# P0_1.net
KiCad netlist of a schematic drawn in EAGLE
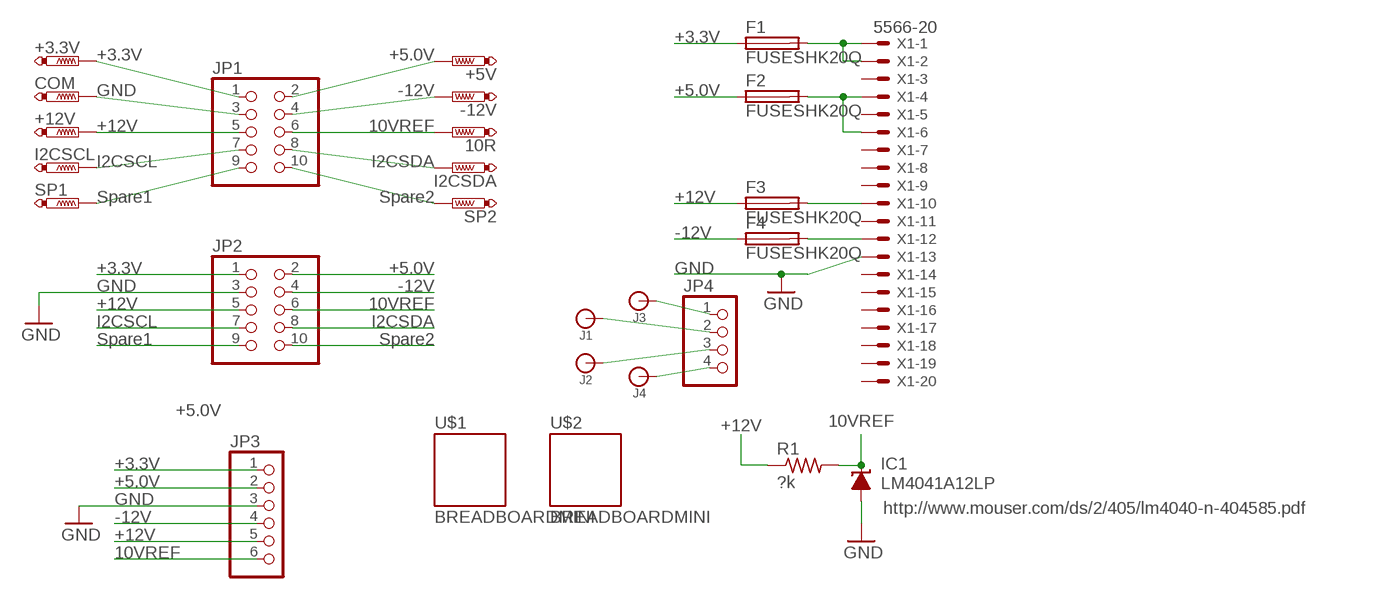
[diagram p0: schematic, sheet 1]

(export (version "E")
  (design (tool "Eeschema 10.0.6"))
  (components
    (comp (ref "+3.3V")
      (value "PTR1B1,27")
      (footprint "eagle-import:B1,27")
      (libsource (lib "eagle-import") (part "PTR1B1,27"))
    )
    (comp (ref "+5V")
      (value "PTR1B1,27")
      (footprint "eagle-import:B1,27")
      (libsource (lib "eagle-import") (part "PTR1B1,27"))
    )
    (comp (ref "+12V")
      (value "PTR1B1,27")
      (footprint "eagle-import:B1,27")
      (libsource (lib "eagle-import") (part "PTR1B1,27"))
    )
    (comp (ref "-12V")
      (value "PTR1B1,27")
      (footprint "eagle-import:B1,27")
      (libsource (lib "eagle-import") (part "PTR1B1,27"))
    )
    (comp (ref "10R")
      (value "PTR1B1,27")
      (footprint "eagle-import:B1,27")
      (libsource (lib "eagle-import") (part "PTR1B1,27"))
    )
    (comp (ref "COM")
      (value "PTR1B1,27")
      (footprint "eagle-import:B1,27")
      (libsource (lib "eagle-import") (part "PTR1B1,27"))
    )
    (comp (ref "F1")
      (value "FUSESHK20Q")
      (footprint "eagle-import:SHK20Q")
      (libsource (lib "eagle-import") (part "FUSESHK20Q"))
    )
    (comp (ref "F2")
      (value "FUSESHK20Q")
      (footprint "eagle-import:SHK20Q")
      (libsource (lib "eagle-import") (part "FUSESHK20Q"))
    )
    (comp (ref "F3")
      (value "FUSESHK20Q")
      (footprint "eagle-import:SHK20Q")
      (libsource (lib "eagle-import") (part "FUSESHK20Q"))
    )
    (comp (ref "F4")
      (value "FUSESHK20Q")
      (footprint "eagle-import:SHK20Q")
      (libsource (lib "eagle-import") (part "FUSESHK20Q"))
    )
    (comp (ref "I2CSCL")
      (value "PTR1B1,27")
      (footprint "eagle-import:B1,27")
      (libsource (lib "eagle-import") (part "PTR1B1,27"))
    )
    (comp (ref "I2CSDA")
      (value "PTR1B1,27")
      (footprint "eagle-import:B1,27")
      (libsource (lib "eagle-import") (part "PTR1B1,27"))
    )
    (comp (ref "IC1")
      (value "LM4041A12LP")
      (footprint "eagle-import:LP_O-PBCY-W3")
      (libsource (lib "eagle-import") (part "LM4041LPA12"))
    )
    (comp (ref "J1")
      (value "BANANA_CONN")
      (footprint "eagle-import:BANANA_CONN")
      (libsource (lib "eagle-import") (part "BANANA_CONN"))
    )
    (comp (ref "J2")
      (value "BANANA_CONN")
      (footprint "eagle-import:BANANA_CONN")
      (libsource (lib "eagle-import") (part "BANANA_CONN"))
    )
    (comp (ref "J3")
      (value "BANANA_CONN")
      (footprint "eagle-import:BANANA_CONN")
      (libsource (lib "eagle-import") (part "BANANA_CONN"))
    )
    (comp (ref "J4")
      (value "BANANA_CONN")
      (footprint "eagle-import:BANANA_CONN")
      (libsource (lib "eagle-import") (part "BANANA_CONN"))
    )
    (comp (ref "JP1")
      (value "PINHD-2X5/90")
      (footprint "eagle-import:2X05_90")
      (libsource (lib "eagle-import") (part "PINHD-2X5/90"))
    )
    (comp (ref "JP2")
      (value "PINHD-2X5/90")
      (footprint "eagle-import:2X05_90")
      (libsource (lib "eagle-import") (part "PINHD-2X5/90"))
    )
    (comp (ref "JP3")
      (value "PINHD-1X6")
      (footprint "eagle-import:1X06")
      (libsource (lib "eagle-import") (part "PINHD-1X6"))
    )
    (comp (ref "JP4")
      (value "PINHD-1X4")
      (footprint "eagle-import:1X04")
      (libsource (lib "eagle-import") (part "PINHD-1X4"))
    )
    (comp (ref "R1")
      (value "?k")
      (footprint "eagle-import:0204_7")
      (libsource (lib "eagle-import") (part "R-US_0204/7"))
    )
    (comp (ref "SP1")
      (value "PTR1B1,27")
      (footprint "eagle-import:B1,27")
      (libsource (lib "eagle-import") (part "PTR1B1,27"))
    )
    (comp (ref "SP2")
      (value "PTR1B1,27")
      (footprint "eagle-import:B1,27")
      (libsource (lib "eagle-import") (part "PTR1B1,27"))
    )
    (comp (ref "U$1")
      (value "BREADBOARDMINI")
      (footprint "eagle-import:BREADBOARD-MINI")
      (libsource (lib "eagle-import") (part "BREADBOARDMINI"))
    )
    (comp (ref "U$2")
      (value "BREADBOARDMINI")
      (footprint "eagle-import:BREADBOARD-MINI")
      (libsource (lib "eagle-import") (part "BREADBOARDMINI"))
    )
    (comp (ref "X1")
      (value "5566-20")
      (footprint "eagle-import:5566-20")
      (libsource (lib "eagle-import") (part "5566-20"))
    )
  )
  (nets
    (net (code "1") (name "/+3.3V") (class "Default")
      (node (ref "+3.3V") (pin "TP") (pinfunction "TP_TP") (pintype "input"))
      (node (ref "F1") (pin "1A") (pinfunction "1_1A") (pintype "passive"))
      (node (ref "JP1") (pin "1") (pinfunction "1_1") (pintype "passive"))
      (node (ref "JP2") (pin "1") (pinfunction "1_1") (pintype "passive"))
      (node (ref "JP3") (pin "1") (pinfunction "1_1") (pintype "passive"))
    )
    (net (code "2") (name "/+5.0V") (class "Default")
      (node (ref "+5V") (pin "TP") (pinfunction "TP_TP") (pintype "input"))
      (node (ref "F2") (pin "1A") (pinfunction "1_1A") (pintype "passive"))
      (node (ref "JP1") (pin "2") (pinfunction "2_2") (pintype "passive"))
      (node (ref "JP2") (pin "2") (pinfunction "2_2") (pintype "passive"))
      (node (ref "JP3") (pin "2") (pinfunction "2_2") (pintype "passive"))
    )
    (net (code "3") (name "/+12V") (class "Default")
      (node (ref "+12V") (pin "TP") (pinfunction "TP_TP") (pintype "input"))
      (node (ref "F3") (pin "1A") (pinfunction "1_1A") (pintype "passive"))
      (node (ref "JP1") (pin "5") (pinfunction "5_5") (pintype "passive"))
      (node (ref "JP2") (pin "5") (pinfunction "5_5") (pintype "passive"))
      (node (ref "JP3") (pin "5") (pinfunction "5_5") (pintype "passive"))
      (node (ref "R1") (pin "1") (pinfunction "1_1") (pintype "passive"))
    )
    (net (code "4") (name "/-12V") (class "Default")
      (node (ref "-12V") (pin "TP") (pinfunction "TP_TP") (pintype "input"))
      (node (ref "F4") (pin "1A") (pinfunction "1_1A") (pintype "passive"))
      (node (ref "JP1") (pin "4") (pinfunction "4_4") (pintype "passive"))
      (node (ref "JP2") (pin "4") (pinfunction "4_4") (pintype "passive"))
      (node (ref "JP3") (pin "4") (pinfunction "4_4") (pintype "passive"))
    )
    (net (code "5") (name "/10VREF") (class "Default")
      (node (ref "10R") (pin "TP") (pinfunction "TP_TP") (pintype "input"))
      (node (ref "IC1") (pin "2") (pinfunction "C_2") (pintype "passive"))
      (node (ref "JP1") (pin "6") (pinfunction "6_6") (pintype "passive"))
      (node (ref "JP2") (pin "6") (pinfunction "6_6") (pintype "passive"))
      (node (ref "JP3") (pin "6") (pinfunction "6_6") (pintype "passive"))
      (node (ref "R1") (pin "2") (pinfunction "2_2") (pintype "passive"))
    )
    (net (code "6") (name "/I2CSCL") (class "Default")
      (node (ref "I2CSCL") (pin "TP") (pinfunction "TP_TP") (pintype "input"))
      (node (ref "JP1") (pin "7") (pinfunction "7_7") (pintype "passive"))
      (node (ref "JP2") (pin "7") (pinfunction "7_7") (pintype "passive"))
    )
    (net (code "7") (name "/I2CSDA") (class "Default")
      (node (ref "I2CSDA") (pin "TP") (pinfunction "TP_TP") (pintype "input"))
      (node (ref "JP1") (pin "8") (pinfunction "8_8") (pintype "passive"))
      (node (ref "JP2") (pin "8") (pinfunction "8_8") (pintype "passive"))
    )
    (net (code "8") (name "/SPARE1") (class "Default")
      (node (ref "JP1") (pin "9") (pinfunction "9_9") (pintype "passive"))
      (node (ref "JP2") (pin "9") (pinfunction "9_9") (pintype "passive"))
      (node (ref "SP1") (pin "TP") (pinfunction "TP_TP") (pintype "input"))
    )
    (net (code "9") (name "/SPARE2") (class "Default")
      (node (ref "JP1") (pin "10") (pinfunction "10_10") (pintype "passive"))
      (node (ref "JP2") (pin "10") (pinfunction "10_10") (pintype "passive"))
      (node (ref "SP2") (pin "TP") (pinfunction "TP_TP") (pintype "input"))
    )
    (net (code "10") (name "GND") (class "Default")
      (node (ref "COM") (pin "TP") (pinfunction "TP_TP") (pintype "input"))
      (node (ref "IC1") (pin "3") (pinfunction "A_3") (pintype "passive"))
      (node (ref "JP1") (pin "3") (pinfunction "3_3") (pintype "passive"))
      (node (ref "JP2") (pin "3") (pinfunction "3_3") (pintype "passive"))
      (node (ref "JP3") (pin "3") (pinfunction "3_3") (pintype "passive"))
      (node (ref "X1") (pin "13") (pinfunction "S_13") (pintype "passive"))
    )
    (net (code "11") (name "Net-(F1-2)") (class "Default")
      (node (ref "F1") (pin "2A") (pinfunction "2_2A") (pintype "passive"))
      (node (ref "X1") (pin "1") (pinfunction "S_1") (pintype "passive"))
      (node (ref "X1") (pin "2") (pinfunction "S_2") (pintype "passive"))
    )
    (net (code "12") (name "Net-(F2-2)") (class "Default")
      (node (ref "F2") (pin "2A") (pinfunction "2_2A") (pintype "passive"))
      (node (ref "X1") (pin "4") (pinfunction "S_4") (pintype "passive"))
      (node (ref "X1") (pin "6") (pinfunction "S_6") (pintype "passive"))
    )
    (net (code "13") (name "Net-(F3-2)") (class "Default")
      (node (ref "F3") (pin "2A") (pinfunction "2_2A") (pintype "passive"))
      (node (ref "X1") (pin "10") (pinfunction "S_10") (pintype "passive"))
    )
    (net (code "14") (name "Net-(F4-2)") (class "Default")
      (node (ref "F4") (pin "2A") (pinfunction "2_2A") (pintype "passive"))
      (node (ref "X1") (pin "12") (pinfunction "S_12") (pintype "passive"))
    )
    (net (code "15") (name "Net-(J1-1)") (class "Default")
      (node (ref "J1") (pin "P$1") (pinfunction "1_P$1") (pintype "passive"))
      (node (ref "JP4") (pin "2") (pinfunction "2_2") (pintype "passive"))
    )
    (net (code "16") (name "Net-(J2-1)") (class "Default")
      (node (ref "J2") (pin "P$1") (pinfunction "1_P$1") (pintype "passive"))
      (node (ref "JP4") (pin "3") (pinfunction "3_3") (pintype "passive"))
    )
    (net (code "17") (name "Net-(J3-1)") (class "Default")
      (node (ref "J3") (pin "P$1") (pinfunction "1_P$1") (pintype "passive"))
      (node (ref "JP4") (pin "1") (pinfunction "1_1") (pintype "passive"))
    )
    (net (code "18") (name "Net-(J4-1)") (class "Default")
      (node (ref "J4") (pin "P$1") (pinfunction "1_P$1") (pintype "passive"))
      (node (ref "JP4") (pin "4") (pinfunction "4_4") (pintype "passive"))
    )
    (net (code "19") (name "unconnected-(X1C-S-Pad11)") (class "Default")
      (node (ref "X1") (pin "11") (pinfunction "S_11") (pintype "passive"))
    )
    (net (code "20") (name "unconnected-(X1F-S-Pad14)") (class "Default")
      (node (ref "X1") (pin "14") (pinfunction "S_14") (pintype "passive"))
    )
    (net (code "21") (name "unconnected-(X1G-S-Pad15)") (class "Default")
      (node (ref "X1") (pin "15") (pinfunction "S_15") (pintype "passive"))
    )
    (net (code "22") (name "unconnected-(X1H-S-Pad16)") (class "Default")
      (node (ref "X1") (pin "16") (pinfunction "S_16") (pintype "passive"))
    )
    (net (code "23") (name "unconnected-(X1I-S-Pad17)") (class "Default")
      (node (ref "X1") (pin "17") (pinfunction "S_17") (pintype "passive"))
    )
    (net (code "24") (name "unconnected-(X1J-S-Pad18)") (class "Default")
      (node (ref "X1") (pin "18") (pinfunction "S_18") (pintype "passive"))
    )
    (net (code "25") (name "unconnected-(X1K-S-Pad19)") (class "Default")
      (node (ref "X1") (pin "19") (pinfunction "S_19") (pintype "passive"))
    )
    (net (code "26") (name "unconnected-(X1M-S-Pad20)") (class "Default")
      (node (ref "X1") (pin "20") (pinfunction "S_20") (pintype "passive"))
    )
    (net (code "27") (name "unconnected-(X1N-S-Pad3)") (class "Default")
      (node (ref "X1") (pin "3") (pinfunction "S_3") (pintype "passive"))
    )
    (net (code "28") (name "unconnected-(X1P-S-Pad5)") (class "Default")
      (node (ref "X1") (pin "5") (pinfunction "S_5") (pintype "passive"))
    )
    (net (code "29") (name "unconnected-(X1R-S-Pad7)") (class "Default")
      (node (ref "X1") (pin "7") (pinfunction "S_7") (pintype "passive"))
    )
    (net (code "30") (name "unconnected-(X1S-S-Pad8)") (class "Default")
      (node (ref "X1") (pin "8") (pinfunction "S_8") (pintype "passive"))
    )
    (net (code "31") (name "unconnected-(X1T-S-Pad9)") (class "Default")
      (node (ref "X1") (pin "9") (pinfunction "S_9") (pintype "passive"))
    )
  )
)
